# PCB-ENCODER-C.net
KiCad netlist of a schematic drawn in EAGLE
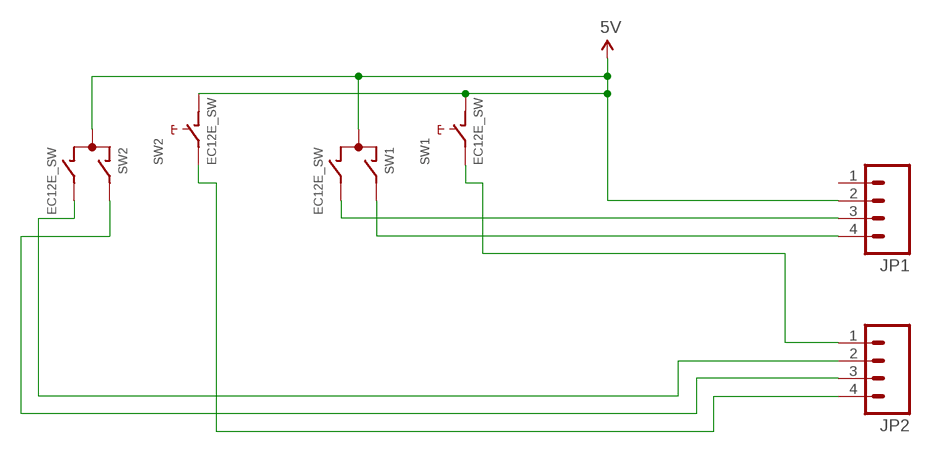
[diagram p0: schematic, sheet 1]

(export (version "E")
  (design (tool "Eeschema 10.0.6"))
  (components
    (comp (ref "JP1")
      (value "M04PTH")
      (footprint "eagle-import:1X04")
      (libsource (lib "eagle-import") (part "M04PTH"))
    )
    (comp (ref "JP2")
      (value "M04PTH")
      (footprint "eagle-import:1X04")
      (libsource (lib "eagle-import") (part "M04PTH"))
    )
    (comp (ref "SW1")
      (value "EC12E_SW")
      (footprint "eagle-import:ALPS_EC12E_SW")
      (fields (field (name "MPN") "EC12E2424407"))
      (libsource (lib "eagle-import") (part "EC12E_SW"))
    )
    (comp (ref "SW2")
      (value "EC12E_SW")
      (footprint "eagle-import:ALPS_EC12E_SW")
      (fields (field (name "MPN") "EC12E2424407"))
      (libsource (lib "eagle-import") (part "EC12E_SW"))
    )
  )
  (nets
    (net (code "1") (name "5V") (class "Default")
      (node (ref "JP1") (pin "2") (pinfunction "2_2") (pintype "passive"))
      (node (ref "SW1") (pin "C") (pinfunction "C_C") (pintype "passive"))
      (node (ref "SW1") (pin "D") (pinfunction "1_D") (pintype "passive"))
      (node (ref "SW2") (pin "C") (pinfunction "C_C") (pintype "passive"))
      (node (ref "SW2") (pin "D") (pinfunction "1_D") (pintype "passive"))
    )
    (net (code "2") (name "Net-(JP1-Pad3)") (class "Default")
      (node (ref "JP1") (pin "3") (pinfunction "3_3") (pintype "passive"))
      (node (ref "SW1") (pin "B") (pinfunction "B_B") (pintype "passive"))
    )
    (net (code "3") (name "Net-(JP1-Pad4)") (class "Default")
      (node (ref "JP1") (pin "4") (pinfunction "4_4") (pintype "passive"))
      (node (ref "SW1") (pin "A") (pinfunction "A_A") (pintype "passive"))
    )
    (net (code "4") (name "Net-(JP2-Pad2)") (class "Default")
      (node (ref "JP2") (pin "2") (pinfunction "2_2") (pintype "passive"))
      (node (ref "SW2") (pin "B") (pinfunction "B_B") (pintype "passive"))
    )
    (net (code "5") (name "Net-(JP2-Pad3)") (class "Default")
      (node (ref "JP2") (pin "3") (pinfunction "3_3") (pintype "passive"))
      (node (ref "SW2") (pin "A") (pinfunction "A_A") (pintype "passive"))
    )
    (net (code "6") (name "Net-(SW1B-2)") (class "Default")
      (node (ref "JP2") (pin "1") (pinfunction "1_1") (pintype "passive"))
      (node (ref "SW1") (pin "E") (pinfunction "2_E") (pintype "passive"))
    )
    (net (code "7") (name "Net-(SW2B-2)") (class "Default")
      (node (ref "JP2") (pin "4") (pinfunction "4_4") (pintype "passive"))
      (node (ref "SW2") (pin "E") (pinfunction "2_E") (pintype "passive"))
    )
    (net (code "8") (name "unconnected-(JP1-Pad1)") (class "Default")
      (node (ref "JP1") (pin "1") (pinfunction "1_1") (pintype "passive"))
    )
  )
)
